# Main.net
KiCad netlist of a schematic drawn in Altium Designer
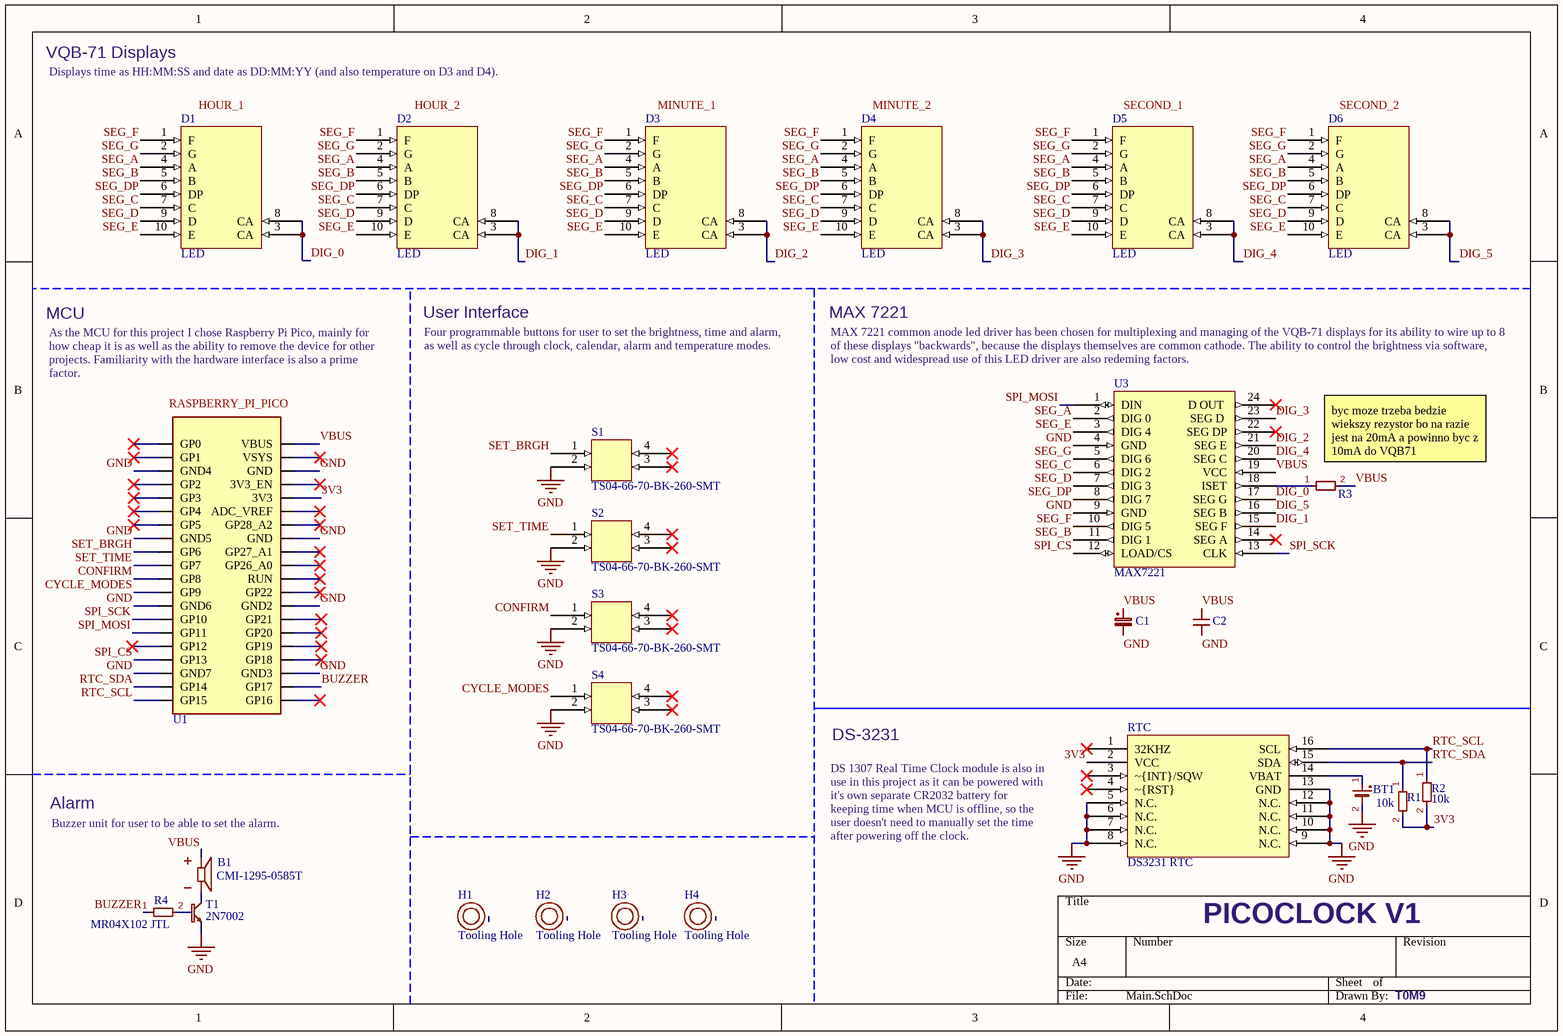
[diagram p0: Main.SchDoc]

(export (version "E")
  (design (tool "Eeschema 10.0.6"))
  (components
    (comp (ref "B1")
      (value "CMI-1295-0585T")
      (footprint "CMI-1295-0585T")
      (description "Buzzer")
      (libsource (lib "Schlib1") (part "CMI-1295-0585T"))
    )
    (comp (ref "BT1")
      (value "Keystone 3034 BH")
      (footprint "BAT_3034TR")
      (libsource (lib "Schlib1") (part "Keystone 3034 BH"))
    )
    (comp (ref "C1")
      (value "Electrolitic Capacitor 10uF")
      (footprint "CAPC2012X145N")
      (description "CGA4J1X7R0J106K125AC \r\n\r\n10u 6.3V 0805")
      (libsource (lib "Schlib1") (part "Electrolitic Capacitor 10uF"))
    )
    (comp (ref "C2")
      (value "UMK105B7104KVHF")
      (footprint "UMK105B7104KVHF")
      (description "0.1uF")
      (libsource (lib "Schlib1") (part "UMK105B7104KVHF"))
    )
    (comp (ref "D1")
      (value "LED")
      (footprint "LED_INND-TS56RAB")
      (description "VQB-71")
      (libsource (lib "Schlib1") (part "LED"))
    )
    (comp (ref "D2")
      (value "LED")
      (footprint "LED_INND-TS56RAB")
      (description "VQB-71")
      (libsource (lib "Schlib1") (part "LED"))
    )
    (comp (ref "D3")
      (value "LED")
      (footprint "LED_INND-TS56RAB")
      (description "VQB-71")
      (libsource (lib "Schlib1") (part "LED"))
    )
    (comp (ref "D4")
      (value "LED")
      (footprint "LED_INND-TS56RAB")
      (description "VQB-71")
      (libsource (lib "Schlib1") (part "LED"))
    )
    (comp (ref "D5")
      (value "LED")
      (footprint "LED_INND-TS56RAB")
      (description "VQB-71")
      (libsource (lib "Schlib1") (part "LED"))
    )
    (comp (ref "D6")
      (value "LED")
      (footprint "LED_INND-TS56RAB")
      (description "VQB-71")
      (libsource (lib "Schlib1") (part "LED"))
    )
    (comp (ref "H1")
      (value "Tooling Hole")
      (footprint "Tooling Hole")
      (libsource (lib "Schlib1") (part "Tooling Hole"))
    )
    (comp (ref "H2")
      (value "Tooling Hole")
      (footprint "Tooling Hole")
      (libsource (lib "Schlib1") (part "Tooling Hole"))
    )
    (comp (ref "H3")
      (value "Tooling Hole")
      (footprint "Tooling Hole")
      (libsource (lib "Schlib1") (part "Tooling Hole"))
    )
    (comp (ref "H4")
      (value "Tooling Hole")
      (footprint "Tooling Hole")
      (libsource (lib "Schlib1") (part "Tooling Hole"))
    )
    (comp (ref "R1")
      (value "10k")
      (footprint "MR04X102 JTL")
      (libsource (lib "Schlib1") (part "ESR01MZPF1002"))
    )
    (comp (ref "R2")
      (value "10k")
      (footprint "MR04X102 JTL")
      (libsource (lib "Schlib1") (part "ESR01MZPF1002"))
    )
    (comp (ref "R3")
      (value "CRCW040221K0FKEDC")
      (footprint "CRCW040221K0FKEDC")
      (description "21k")
      (libsource (lib "Schlib1") (part "CRCW040221K0FKEDC"))
    )
    (comp (ref "R4")
      (value "MR04X102 JTL")
      (footprint "MR04X102 JTL")
      (description "1k")
      (libsource (lib "Schlib1") (part "MR04X102 JTL"))
    )
    (comp (ref "RTC")
      (value "DS3231 RTC")
      (footprint "DS3231 RTC")
      (libsource (lib "Schlib1") (part "DS3231 RTC"))
    )
    (comp (ref "S1")
      (value "TS04-66-70-BK-260-SMT")
      (footprint "TS04-66-70-BK-260-SMT")
      (description "50mA 12VDC")
      (libsource (lib "Schlib1") (part "TS04-66-70-BK-260-SMT"))
    )
    (comp (ref "S2")
      (value "TS04-66-70-BK-260-SMT")
      (footprint "TS04-66-70-BK-260-SMT")
      (description "50mA 12VDC")
      (libsource (lib "Schlib1") (part "TS04-66-70-BK-260-SMT"))
    )
    (comp (ref "S3")
      (value "TS04-66-70-BK-260-SMT")
      (footprint "TS04-66-70-BK-260-SMT")
      (description "50mA 12VDC")
      (libsource (lib "Schlib1") (part "TS04-66-70-BK-260-SMT"))
    )
    (comp (ref "S4")
      (value "TS04-66-70-BK-260-SMT")
      (footprint "TS04-66-70-BK-260-SMT")
      (description "50mA 12VDC")
      (libsource (lib "Schlib1") (part "TS04-66-70-BK-260-SMT"))
    )
    (comp (ref "T1")
      (value "2N7002")
      (footprint "2N7002")
      (description "Transistor")
      (libsource (lib "Schlib1") (part "2N7002"))
    )
    (comp (ref "U1")
      (value "RASPBERRY_PI_PICO")
      (footprint "RASPBERRY_PI_PICO")
      (fields (field (name "MF") "Raspberry Pi") (field (name "MP") "RASPBERRY PI PICO"))
      (libsource (lib "Schlib1") (part "RASPBERRY_PI_PICO"))
    )
    (comp (ref "U3") (value "MAX7221") (footprint "MAX7221") (libsource (lib "Schlib1") (part "MAX7221")))
  )
  (nets
    (net (code "1") (name "/3V3") (class "Default")
      (node (ref "R1") (pin "2") (pinfunction "2_2") (pintype "passive"))
      (node (ref "R2") (pin "2") (pinfunction "2_2") (pintype "passive"))
      (node (ref "RTC") (pin "2") (pinfunction "VCC_2") (pintype "power_in"))
      (node (ref "U1") (pin "3V3") (pinfunction "3V3_3V3") (pintype "power_in"))
    )
    (net (code "2") (name "/BUZZER") (class "Default")
      (node (ref "R4") (pin "1") (pinfunction "1_1") (pintype "passive"))
      (node (ref "U1") (pin "GP17") (pinfunction "GP17_GP17") (pintype "bidirectional"))
    )
    (net (code "3") (name "/CONFIRM") (class "Default")
      (node (ref "S3") (pin "1") (pintype "input"))
      (node (ref "U1") (pin "GP8") (pinfunction "GP8_GP8") (pintype "bidirectional"))
    )
    (net (code "4") (name "/CYCLE_MODES") (class "Default")
      (node (ref "S4") (pin "1") (pintype "input"))
      (node (ref "U1") (pin "GP9") (pinfunction "GP9_GP9") (pintype "bidirectional"))
    )
    (net (code "5") (name "/DIG_0") (class "Default")
      (node (ref "D1") (pin "3") (pinfunction "CA_3") (pintype "input"))
      (node (ref "D1") (pin "8") (pinfunction "CA_8") (pintype "input"))
      (node (ref "U3") (pin "17") (pinfunction "SEG_G_17") (pintype "output"))
    )
    (net (code "6") (name "/DIG_1") (class "Default")
      (node (ref "D2") (pin "3") (pinfunction "CA_3") (pintype "input"))
      (node (ref "D2") (pin "8") (pinfunction "CA_8") (pintype "input"))
      (node (ref "U3") (pin "15") (pinfunction "SEG_F_15") (pintype "output"))
    )
    (net (code "7") (name "/DIG_2") (class "Default")
      (node (ref "D3") (pin "3") (pinfunction "CA_3") (pintype "input"))
      (node (ref "D3") (pin "8") (pinfunction "CA_8") (pintype "input"))
      (node (ref "U3") (pin "21") (pinfunction "SEG_E_21") (pintype "output"))
    )
    (net (code "8") (name "/DIG_3") (class "Default")
      (node (ref "D4") (pin "3") (pinfunction "CA_3") (pintype "input"))
      (node (ref "D4") (pin "8") (pinfunction "CA_8") (pintype "input"))
      (node (ref "U3") (pin "23") (pinfunction "SEG_D_23") (pintype "output"))
    )
    (net (code "9") (name "/DIG_4") (class "Default")
      (node (ref "D5") (pin "3") (pinfunction "CA_3") (pintype "input"))
      (node (ref "D5") (pin "8") (pinfunction "CA_8") (pintype "input"))
      (node (ref "U3") (pin "20") (pinfunction "SEG_C_20") (pintype "output"))
    )
    (net (code "10") (name "/DIG_5") (class "Default")
      (node (ref "D6") (pin "3") (pinfunction "CA_3") (pintype "input"))
      (node (ref "D6") (pin "8") (pinfunction "CA_8") (pintype "input"))
      (node (ref "U3") (pin "16") (pinfunction "SEG_B_16") (pintype "output"))
    )
    (net (code "11") (name "/RTC_SCL") (class "Default")
      (node (ref "R2") (pin "1") (pinfunction "1_1") (pintype "passive"))
      (node (ref "RTC") (pin "16") (pinfunction "SCL_16") (pintype "input"))
      (node (ref "U1") (pin "GP15") (pinfunction "GP15_GP15") (pintype "bidirectional"))
    )
    (net (code "12") (name "/RTC_SDA") (class "Default")
      (node (ref "R1") (pin "1") (pinfunction "1_1") (pintype "passive"))
      (node (ref "RTC") (pin "15") (pinfunction "SDA_15") (pintype "bidirectional"))
      (node (ref "U1") (pin "GP14") (pinfunction "GP14_GP14") (pintype "bidirectional"))
    )
    (net (code "13") (name "/SEG_A") (class "Default")
      (node (ref "D1") (pin "4") (pinfunction "A_4") (pintype "input"))
      (node (ref "D2") (pin "4") (pinfunction "A_4") (pintype "input"))
      (node (ref "D3") (pin "4") (pinfunction "A_4") (pintype "input"))
      (node (ref "D4") (pin "4") (pinfunction "A_4") (pintype "input"))
      (node (ref "D5") (pin "4") (pinfunction "A_4") (pintype "input"))
      (node (ref "D6") (pin "4") (pinfunction "A_4") (pintype "input"))
      (node (ref "U3") (pin "2") (pinfunction "DIG_0_2") (pintype "output"))
    )
    (net (code "14") (name "/SEG_B") (class "Default")
      (node (ref "D1") (pin "5") (pinfunction "B_5") (pintype "input"))
      (node (ref "D2") (pin "5") (pinfunction "B_5") (pintype "input"))
      (node (ref "D3") (pin "5") (pinfunction "B_5") (pintype "input"))
      (node (ref "D4") (pin "5") (pinfunction "B_5") (pintype "input"))
      (node (ref "D5") (pin "5") (pinfunction "B_5") (pintype "input"))
      (node (ref "D6") (pin "5") (pinfunction "B_5") (pintype "input"))
      (node (ref "U3") (pin "11") (pinfunction "DIG_1_11") (pintype "output"))
    )
    (net (code "15") (name "/SEG_C") (class "Default")
      (node (ref "D1") (pin "7") (pinfunction "C_7") (pintype "input"))
      (node (ref "D2") (pin "7") (pinfunction "C_7") (pintype "input"))
      (node (ref "D3") (pin "7") (pinfunction "C_7") (pintype "input"))
      (node (ref "D4") (pin "7") (pinfunction "C_7") (pintype "input"))
      (node (ref "D5") (pin "7") (pinfunction "C_7") (pintype "input"))
      (node (ref "D6") (pin "7") (pinfunction "C_7") (pintype "input"))
      (node (ref "U3") (pin "6") (pinfunction "DIG_2_6") (pintype "output"))
    )
    (net (code "16") (name "/SEG_D") (class "Default")
      (node (ref "D1") (pin "9") (pinfunction "D_9") (pintype "input"))
      (node (ref "D2") (pin "9") (pinfunction "D_9") (pintype "input"))
      (node (ref "D3") (pin "9") (pinfunction "D_9") (pintype "input"))
      (node (ref "D4") (pin "9") (pinfunction "D_9") (pintype "input"))
      (node (ref "D5") (pin "9") (pinfunction "D_9") (pintype "input"))
      (node (ref "D6") (pin "9") (pinfunction "D_9") (pintype "input"))
      (node (ref "U3") (pin "7") (pinfunction "DIG_3_7") (pintype "output"))
    )
    (net (code "17") (name "/SEG_DP") (class "Default")
      (node (ref "D1") (pin "6") (pinfunction "DP_6") (pintype "input"))
      (node (ref "D2") (pin "6") (pinfunction "DP_6") (pintype "input"))
      (node (ref "D3") (pin "6") (pinfunction "DP_6") (pintype "input"))
      (node (ref "D4") (pin "6") (pinfunction "DP_6") (pintype "input"))
      (node (ref "D5") (pin "6") (pinfunction "DP_6") (pintype "input"))
      (node (ref "D6") (pin "6") (pinfunction "DP_6") (pintype "input"))
      (node (ref "U3") (pin "8") (pinfunction "DIG_7_8") (pintype "output"))
    )
    (net (code "18") (name "/SEG_E") (class "Default")
      (node (ref "D1") (pin "10") (pinfunction "E_10") (pintype "input"))
      (node (ref "D2") (pin "10") (pinfunction "E_10") (pintype "input"))
      (node (ref "D3") (pin "10") (pinfunction "E_10") (pintype "input"))
      (node (ref "D4") (pin "10") (pinfunction "E_10") (pintype "input"))
      (node (ref "D5") (pin "10") (pinfunction "E_10") (pintype "input"))
      (node (ref "D6") (pin "10") (pinfunction "E_10") (pintype "input"))
      (node (ref "U3") (pin "3") (pinfunction "DIG_4_3") (pintype "output"))
    )
    (net (code "19") (name "/SEG_F") (class "Default")
      (node (ref "D1") (pin "1") (pinfunction "F_1") (pintype "input"))
      (node (ref "D2") (pin "1") (pinfunction "F_1") (pintype "input"))
      (node (ref "D3") (pin "1") (pinfunction "F_1") (pintype "input"))
      (node (ref "D4") (pin "1") (pinfunction "F_1") (pintype "input"))
      (node (ref "D5") (pin "1") (pinfunction "F_1") (pintype "input"))
      (node (ref "D6") (pin "1") (pinfunction "F_1") (pintype "input"))
      (node (ref "U3") (pin "10") (pinfunction "DIG_5_10") (pintype "output"))
    )
    (net (code "20") (name "/SEG_G") (class "Default")
      (node (ref "D1") (pin "2") (pinfunction "G_2") (pintype "input"))
      (node (ref "D2") (pin "2") (pinfunction "G_2") (pintype "input"))
      (node (ref "D3") (pin "2") (pinfunction "G_2") (pintype "input"))
      (node (ref "D4") (pin "2") (pinfunction "G_2") (pintype "input"))
      (node (ref "D5") (pin "2") (pinfunction "G_2") (pintype "input"))
      (node (ref "D6") (pin "2") (pinfunction "G_2") (pintype "input"))
      (node (ref "U3") (pin "5") (pinfunction "DIG_6_5") (pintype "output"))
    )
    (net (code "21") (name "/SET_BRGH") (class "Default")
      (node (ref "S1") (pin "1") (pintype "input"))
      (node (ref "U1") (pin "GP6") (pinfunction "GP6_GP6") (pintype "bidirectional"))
    )
    (net (code "22") (name "/SET_TIME") (class "Default")
      (node (ref "S2") (pin "1") (pintype "input"))
      (node (ref "U1") (pin "GP7") (pinfunction "GP7_GP7") (pintype "bidirectional"))
    )
    (net (code "23") (name "/SPI_CS") (class "Default")
      (node (ref "U1") (pin "GP13") (pinfunction "GP13_GP13") (pintype "bidirectional"))
      (node (ref "U3") (pin "12") (pinfunction "LOAD/CS_12") (pintype "bidirectional"))
    )
    (net (code "24") (name "/SPI_MOSI") (class "Default")
      (node (ref "U1") (pin "GP11") (pinfunction "GP11_GP11") (pintype "bidirectional"))
      (node (ref "U3") (pin "1") (pinfunction "DIN_1") (pintype "bidirectional"))
    )
    (net (code "25") (name "/SPI_SCK") (class "Default")
      (node (ref "U1") (pin "GP10") (pinfunction "GP10_GP10") (pintype "bidirectional"))
      (node (ref "U3") (pin "13") (pinfunction "CLK_13") (pintype "input"))
    )
    (net (code "26") (name "/VBUS") (class "Default")
      (node (ref "B1") (pin "P") (pinfunction "P_P") (pintype "passive"))
      (node (ref "C1") (pin "1") (pinfunction "1_1") (pintype "passive"))
      (node (ref "C2") (pin "1") (pinfunction "1_1") (pintype "passive"))
      (node (ref "R3") (pin "2") (pinfunction "2_2") (pintype "passive"))
      (node (ref "U1") (pin "VBUS") (pinfunction "VBUS_VBUS") (pintype "bidirectional"))
      (node (ref "U3") (pin "19") (pinfunction "VCC_19") (pintype "input"))
    )
    (net (code "27") (name "GND") (class "Default")
      (node (ref "BT1") (pin "2") (pinfunction "2_2") (pintype "passive"))
      (node (ref "C1") (pin "2") (pinfunction "2_2") (pintype "passive"))
      (node (ref "C2") (pin "2") (pinfunction "2_2") (pintype "passive"))
      (node (ref "RTC") (pin "10") (pinfunction "N.C._10") (pintype "input"))
      (node (ref "RTC") (pin "11") (pinfunction "N.C._11") (pintype "input"))
      (node (ref "RTC") (pin "12") (pinfunction "N.C._12") (pintype "input"))
      (node (ref "RTC") (pin "13") (pinfunction "GND_13") (pintype "power_in"))
      (node (ref "RTC") (pin "5") (pinfunction "N.C._5") (pintype "input"))
      (node (ref "RTC") (pin "6") (pinfunction "N.C._6") (pintype "input"))
      (node (ref "RTC") (pin "7") (pinfunction "N.C._7") (pintype "input"))
      (node (ref "RTC") (pin "8") (pinfunction "N.C._8") (pintype "input"))
      (node (ref "RTC") (pin "9") (pinfunction "N.C._9") (pintype "input"))
      (node (ref "S1") (pin "2") (pintype "input"))
      (node (ref "S2") (pin "2") (pintype "input"))
      (node (ref "S3") (pin "2") (pintype "input"))
      (node (ref "S4") (pin "2") (pintype "input"))
      (node (ref "T1") (pin "2") (pinfunction "S_2") (pintype "passive"))
      (node (ref "U1") (pin "GND") (pinfunction "GND_GND") (pintype "passive"))
      (node (ref "U1") (pin "GND2") (pinfunction "GND2_GND2") (pintype "passive"))
      (node (ref "U1") (pin "GND3") (pinfunction "GND3_GND3") (pintype "passive"))
      (node (ref "U1") (pin "GND4") (pinfunction "GND4_GND4") (pintype "passive"))
      (node (ref "U1") (pin "GND5") (pinfunction "GND5_GND5") (pintype "passive"))
      (node (ref "U1") (pin "GND6") (pinfunction "GND6_GND6") (pintype "passive"))
      (node (ref "U1") (pin "GND7") (pinfunction "GND7_GND7") (pintype "passive"))
      (node (ref "U3") (pin "4") (pinfunction "GND_4") (pintype "input"))
      (node (ref "U3") (pin "9") (pinfunction "GND_9") (pintype "input"))
    )
    (net (code "28") (name "Net-(RTC-VBAT)") (class "Default")
      (node (ref "BT1") (pin "1") (pinfunction "1_1") (pintype "passive"))
      (node (ref "RTC") (pin "14") (pinfunction "VBAT_14") (pintype "power_in"))
    )
    (net (code "29") (name "Net-(T1-D)") (class "Default")
      (node (ref "B1") (pin "N") (pinfunction "N_N") (pintype "passive"))
      (node (ref "T1") (pin "3") (pinfunction "D_3") (pintype "passive"))
    )
    (net (code "30") (name "Net-(T1-G)") (class "Default")
      (node (ref "R4") (pin "2") (pinfunction "2_2") (pintype "passive"))
      (node (ref "T1") (pin "1") (pinfunction "G_1") (pintype "passive"))
    )
    (net (code "31") (name "Net-(U3-ISET)") (class "Default")
      (node (ref "R3") (pin "1") (pinfunction "1_1") (pintype "passive"))
      (node (ref "U3") (pin "18") (pinfunction "ISET_18") (pintype "output"))
    )
    (net (code "32") (name "unconnected-(RTC-32KHZ-Pad1)") (class "Default")
      (node (ref "RTC") (pin "1") (pinfunction "32KHZ_1") (pintype "open_collector+no_connect"))
    )
    (net (code "33") (name "unconnected-(RTC-~{INT}{slash}SQW-Pad3)") (class "Default")
      (node (ref "RTC") (pin "3") (pinfunction "~{INT}/SQW_3") (pintype "input+no_connect"))
    )
    (net (code "34") (name "unconnected-(RTC-~{RST}-Pad4)") (class "Default")
      (node (ref "RTC") (pin "4") (pinfunction "~{RST}_4") (pintype "input+no_connect"))
    )
    (net (code "35") (name "unconnected-(S1-Pad3)") (class "Default")
      (node (ref "S1") (pin "3") (pintype "input+no_connect"))
    )
    (net (code "36") (name "unconnected-(S1-Pad4)") (class "Default")
      (node (ref "S1") (pin "4") (pintype "input+no_connect"))
    )
    (net (code "37") (name "unconnected-(S2-Pad3)") (class "Default")
      (node (ref "S2") (pin "3") (pintype "input+no_connect"))
    )
    (net (code "38") (name "unconnected-(S2-Pad4)") (class "Default")
      (node (ref "S2") (pin "4") (pintype "input+no_connect"))
    )
    (net (code "39") (name "unconnected-(S3-Pad3)") (class "Default")
      (node (ref "S3") (pin "3") (pintype "input+no_connect"))
    )
    (net (code "40") (name "unconnected-(S3-Pad4)") (class "Default")
      (node (ref "S3") (pin "4") (pintype "input+no_connect"))
    )
    (net (code "41") (name "unconnected-(S4-Pad3)") (class "Default")
      (node (ref "S4") (pin "3") (pintype "input+no_connect"))
    )
    (net (code "42") (name "unconnected-(S4-Pad4)") (class "Default")
      (node (ref "S4") (pin "4") (pintype "input+no_connect"))
    )
    (net (code "43") (name "unconnected-(U1-Pad3V3_EN)") (class "Default")
      (node (ref "U1") (pin "3V3_EN") (pinfunction "3V3_EN_3V3_EN") (pintype "bidirectional+no_connect"))
    )
    (net (code "44") (name "unconnected-(U1-PadADC_VREF)") (class "Default")
      (node (ref "U1") (pin "ADC_VREF") (pinfunction "ADC_VREF_ADC_VREF") (pintype "bidirectional+no_connect"))
    )
    (net (code "45") (name "unconnected-(U1-PadGP0)") (class "Default")
      (node (ref "U1") (pin "GP0") (pinfunction "GP0_GP0") (pintype "bidirectional+no_connect"))
    )
    (net (code "46") (name "unconnected-(U1-PadGP1)") (class "Default")
      (node (ref "U1") (pin "GP1") (pinfunction "GP1_GP1") (pintype "bidirectional+no_connect"))
    )
    (net (code "47") (name "unconnected-(U1-PadGP2)") (class "Default")
      (node (ref "U1") (pin "GP2") (pinfunction "GP2_GP2") (pintype "bidirectional+no_connect"))
    )
    (net (code "48") (name "unconnected-(U1-PadGP3)") (class "Default")
      (node (ref "U1") (pin "GP3") (pinfunction "GP3_GP3") (pintype "bidirectional+no_connect"))
    )
    (net (code "49") (name "unconnected-(U1-PadGP4)") (class "Default")
      (node (ref "U1") (pin "GP4") (pinfunction "GP4_GP4") (pintype "bidirectional+no_connect"))
    )
    (net (code "50") (name "unconnected-(U1-PadGP5)") (class "Default")
      (node (ref "U1") (pin "GP5") (pinfunction "GP5_GP5") (pintype "bidirectional+no_connect"))
    )
    (net (code "51") (name "unconnected-(U1-PadGP12)") (class "Default")
      (node (ref "U1") (pin "GP12") (pinfunction "GP12_GP12") (pintype "bidirectional+no_connect"))
    )
    (net (code "52") (name "unconnected-(U1-PadGP16)") (class "Default")
      (node (ref "U1") (pin "GP16") (pinfunction "GP16_GP16") (pintype "bidirectional+no_connect"))
    )
    (net (code "53") (name "unconnected-(U1-PadGP18)") (class "Default")
      (node (ref "U1") (pin "GP18") (pinfunction "GP18_GP18") (pintype "bidirectional+no_connect"))
    )
    (net (code "54") (name "unconnected-(U1-PadGP19)") (class "Default")
      (node (ref "U1") (pin "GP19") (pinfunction "GP19_GP19") (pintype "bidirectional+no_connect"))
    )
    (net (code "55") (name "unconnected-(U1-PadGP20)") (class "Default")
      (node (ref "U1") (pin "GP20") (pinfunction "GP20_GP20") (pintype "bidirectional+no_connect"))
    )
    (net (code "56") (name "unconnected-(U1-PadGP21)") (class "Default")
      (node (ref "U1") (pin "GP21") (pinfunction "GP21_GP21") (pintype "bidirectional+no_connect"))
    )
    (net (code "57") (name "unconnected-(U1-PadGP22)") (class "Default")
      (node (ref "U1") (pin "GP22") (pinfunction "GP22_GP22") (pintype "bidirectional+no_connect"))
    )
    (net (code "58") (name "unconnected-(U1-PadGP26_A0)") (class "Default")
      (node (ref "U1") (pin "GP26_A0") (pinfunction "GP26_A0_GP26_A0") (pintype "bidirectional+no_connect"))
    )
    (net (code "59") (name "unconnected-(U1-PadGP27_A1)") (class "Default")
      (node (ref "U1") (pin "GP27_A1") (pinfunction "GP27_A1_GP27_A1") (pintype "bidirectional+no_connect"))
    )
    (net (code "60") (name "unconnected-(U1-PadGP28_A2)") (class "Default")
      (node (ref "U1") (pin "GP28_A2") (pinfunction "GP28_A2_GP28_A2") (pintype "bidirectional+no_connect"))
    )
    (net (code "61") (name "unconnected-(U1-PadRUN)") (class "Default")
      (node (ref "U1") (pin "RUN") (pinfunction "RUN_RUN") (pintype "bidirectional+no_connect"))
    )
    (net (code "62") (name "unconnected-(U1-PadVSYS)") (class "Default")
      (node (ref "U1") (pin "VSYS") (pinfunction "VSYS_VSYS") (pintype "bidirectional+no_connect"))
    )
    (net (code "63") (name "unconnected-(U3-D_OUT-Pad24)") (class "Default")
      (node (ref "U3") (pin "24") (pinfunction "D_OUT_24") (pintype "output+no_connect"))
    )
    (net (code "64") (name "unconnected-(U3-SEG_A-Pad14)") (class "Default")
      (node (ref "U3") (pin "14") (pinfunction "SEG_A_14") (pintype "output+no_connect"))
    )
    (net (code "65") (name "unconnected-(U3-SEG_DP-Pad22)") (class "Default")
      (node (ref "U3") (pin "22") (pinfunction "SEG_DP_22") (pintype "output+no_connect"))
    )
  )
)
